# top_aux_l.net
KiCad netlist of a schematic drawn in Altium Designer
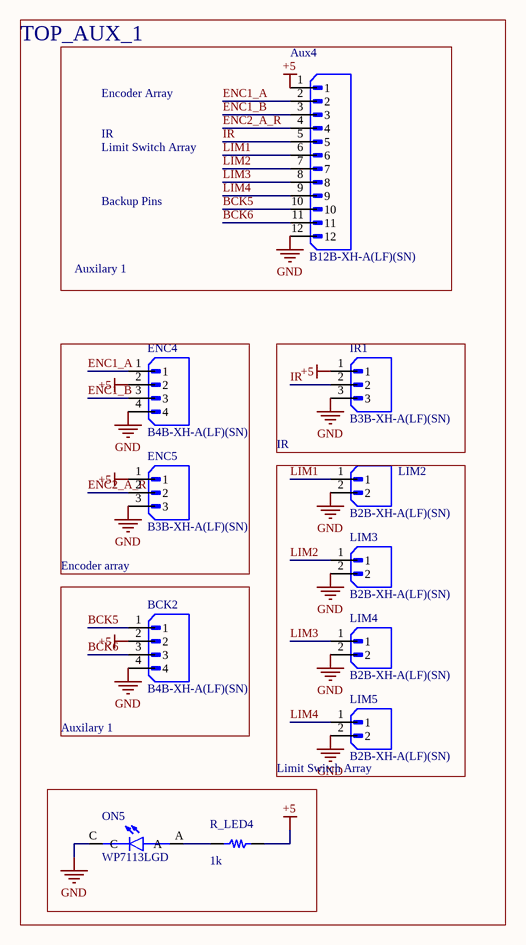
[diagram p0: top_aux_l.SchDoc]

(export (version "E")
  (design (tool "Eeschema 10.0.6"))
  (components
    (comp (ref "Aux4")
      (value "B12B-XH-A(LF)(SN)")
      (footprint "JST_B12B-XH-A(LF)(SN)")
      (description "Connector Header Through Hole 12 position 0.098 (2.50mm)")
      (fields (field (name "MF") "JST Sales"))
      (libsource (lib "CSD Robocon Workspace") (part "B12B-XH-A(LF)(SN)"))
    )
    (comp (ref "BCK2")
      (value "B4B-XH-A(LF)(SN)")
      (footprint "JST_B4B-XH-A(LF)(SN)")
      (description "Connector Header Through Hole 4 position 0.098 (2.50mm)")
      (fields (field (name "MF") "JST Sales"))
      (libsource (lib "CSD Robocon Workspace") (part "B4B-XH-A(LF)(SN)"))
    )
    (comp (ref "ENC4")
      (value "B4B-XH-A(LF)(SN)")
      (footprint "JST_B4B-XH-A(LF)(SN)")
      (description "Connector Header Through Hole 4 position 0.098 (2.50mm)")
      (fields (field (name "MF") "JST Sales"))
      (libsource (lib "CSD Robocon Workspace") (part "B4B-XH-A(LF)(SN)"))
    )
    (comp (ref "ENC5")
      (value "B3B-XH-A(LF)(SN)")
      (footprint "JST_B3B-XH-A(LF)(SN)")
      (description "Connector Header Through Hole 3 position 0.098 (2.50mm)")
      (fields (field (name "MF") "JST Sales"))
      (libsource (lib "CSD Robocon Workspace") (part "B3B-XH-A(LF)(SN)"))
    )
    (comp (ref "IR1")
      (value "B3B-XH-A(LF)(SN)")
      (footprint "JST_B3B-XH-A(LF)(SN)")
      (description "Connector Header Through Hole 3 position 0.098 (2.50mm)")
      (fields (field (name "MF") "JST Sales"))
      (libsource (lib "CSD Robocon Workspace") (part "B3B-XH-A(LF)(SN)"))
    )
    (comp (ref "LIM2")
      (value "B2B-XH-A(LF)(SN)")
      (footprint "JST_B2B-XH-A(LF)(SN)")
      (description "Connector Header Through Hole 2 position 0.098 (2.50mm)")
      (fields (field (name "MF") "JST Sales America Inc."))
      (libsource (lib "CSD Robocon Workspace") (part "B2B-XH-A(LF)(SN)"))
    )
    (comp (ref "LIM3")
      (value "B2B-XH-A(LF)(SN)")
      (footprint "JST_B2B-XH-A(LF)(SN)")
      (description "Connector Header Through Hole 2 position 0.098 (2.50mm)")
      (fields (field (name "MF") "JST Sales America Inc."))
      (libsource (lib "CSD Robocon Workspace") (part "B2B-XH-A(LF)(SN)"))
    )
    (comp (ref "LIM4")
      (value "B2B-XH-A(LF)(SN)")
      (footprint "JST_B2B-XH-A(LF)(SN)")
      (description "Connector Header Through Hole 2 position 0.098 (2.50mm)")
      (fields (field (name "MF") "JST Sales America Inc."))
      (libsource (lib "CSD Robocon Workspace") (part "B2B-XH-A(LF)(SN)"))
    )
    (comp (ref "LIM5")
      (value "B2B-XH-A(LF)(SN)")
      (footprint "JST_B2B-XH-A(LF)(SN)")
      (description "Connector Header Through Hole 2 position 0.098 (2.50mm)")
      (fields (field (name "MF") "JST Sales America Inc."))
      (libsource (lib "CSD Robocon Workspace") (part "B2B-XH-A(LF)(SN)"))
    )
    (comp (ref "ON5")
      (value "WP7113LGD")
      (footprint "LED_WP7113LGD")
      (description "Green 568nm LED Indication - Discrete 1.9V Radial")
      (fields (field (name "MF") "Kingbright"))
      (libsource (lib "CSD Robocon Workspace") (part "WP7113LGD"))
    )
    (comp (ref "R_LED4")
      (value "1k")
      (footprint "generic_res_footprint")
      (description "Generic through hole resistor")
      (libsource (lib "CSD Robocon Workspace") (part "generic_res"))
    )
  )
  (nets
    (net (code "1") (name "+5") (class "Default")
      (node (ref "Aux4") (pin "1") (pinfunction "1_1") (pintype "passive"))
      (node (ref "BCK2") (pin "2") (pinfunction "2_2") (pintype "passive"))
      (node (ref "ENC4") (pin "2") (pinfunction "2_2") (pintype "passive"))
      (node (ref "ENC5") (pin "1") (pinfunction "1_1") (pintype "passive"))
      (node (ref "IR1") (pin "1") (pinfunction "1_1") (pintype "passive"))
      (node (ref "R_LED4") (pin "2") (pinfunction "2_2") (pintype "passive"))
    )
    (net (code "2") (name "/BCK5") (class "Default")
      (node (ref "Aux4") (pin "10") (pinfunction "10_10") (pintype "passive"))
      (node (ref "BCK2") (pin "1") (pinfunction "1_1") (pintype "passive"))
    )
    (net (code "3") (name "/BCK6") (class "Default")
      (node (ref "Aux4") (pin "11") (pinfunction "11_11") (pintype "passive"))
      (node (ref "BCK2") (pin "3") (pinfunction "3_3") (pintype "passive"))
    )
    (net (code "4") (name "/ENC1_A") (class "Default")
      (node (ref "Aux4") (pin "2") (pinfunction "2_2") (pintype "passive"))
      (node (ref "ENC4") (pin "1") (pinfunction "1_1") (pintype "passive"))
    )
    (net (code "5") (name "/ENC1_B") (class "Default")
      (node (ref "Aux4") (pin "3") (pinfunction "3_3") (pintype "passive"))
      (node (ref "ENC4") (pin "3") (pinfunction "3_3") (pintype "passive"))
    )
    (net (code "6") (name "/ENC2_A_R") (class "Default")
      (node (ref "Aux4") (pin "4") (pinfunction "4_4") (pintype "passive"))
      (node (ref "ENC5") (pin "2") (pinfunction "2_2") (pintype "passive"))
    )
    (net (code "7") (name "/IR") (class "Default")
      (node (ref "Aux4") (pin "5") (pinfunction "5_5") (pintype "passive"))
      (node (ref "IR1") (pin "2") (pinfunction "2_2") (pintype "passive"))
    )
    (net (code "8") (name "/LIM1") (class "Default")
      (node (ref "Aux4") (pin "6") (pinfunction "6_6") (pintype "passive"))
      (node (ref "LIM2") (pin "1") (pinfunction "1_1") (pintype "passive"))
    )
    (net (code "9") (name "/LIM2") (class "Default")
      (node (ref "Aux4") (pin "7") (pinfunction "7_7") (pintype "passive"))
      (node (ref "LIM3") (pin "1") (pinfunction "1_1") (pintype "passive"))
    )
    (net (code "10") (name "/LIM3") (class "Default")
      (node (ref "Aux4") (pin "8") (pinfunction "8_8") (pintype "passive"))
      (node (ref "LIM4") (pin "1") (pinfunction "1_1") (pintype "passive"))
    )
    (net (code "11") (name "/LIM4") (class "Default")
      (node (ref "Aux4") (pin "9") (pinfunction "9_9") (pintype "passive"))
      (node (ref "LIM5") (pin "1") (pinfunction "1_1") (pintype "passive"))
    )
    (net (code "12") (name "GND") (class "Default")
      (node (ref "Aux4") (pin "12") (pinfunction "12_12") (pintype "passive"))
      (node (ref "BCK2") (pin "4") (pinfunction "4_4") (pintype "passive"))
      (node (ref "ENC4") (pin "4") (pinfunction "4_4") (pintype "passive"))
      (node (ref "ENC5") (pin "3") (pinfunction "3_3") (pintype "passive"))
      (node (ref "IR1") (pin "3") (pinfunction "3_3") (pintype "passive"))
      (node (ref "LIM2") (pin "2") (pinfunction "2_2") (pintype "passive"))
      (node (ref "LIM3") (pin "2") (pinfunction "2_2") (pintype "passive"))
      (node (ref "LIM4") (pin "2") (pinfunction "2_2") (pintype "passive"))
      (node (ref "LIM5") (pin "2") (pinfunction "2_2") (pintype "passive"))
      (node (ref "ON5") (pin "C") (pinfunction "C_C") (pintype "passive"))
    )
    (net (code "13") (name "Net-(ON5-PadA)") (class "Default")
      (node (ref "ON5") (pin "A") (pinfunction "A_A") (pintype "passive"))
      (node (ref "R_LED4") (pin "1") (pinfunction "1_1") (pintype "passive"))
    )
  )
)
